# CC2650_Protoboard.net
KiCad netlist of a schematic drawn in EAGLE
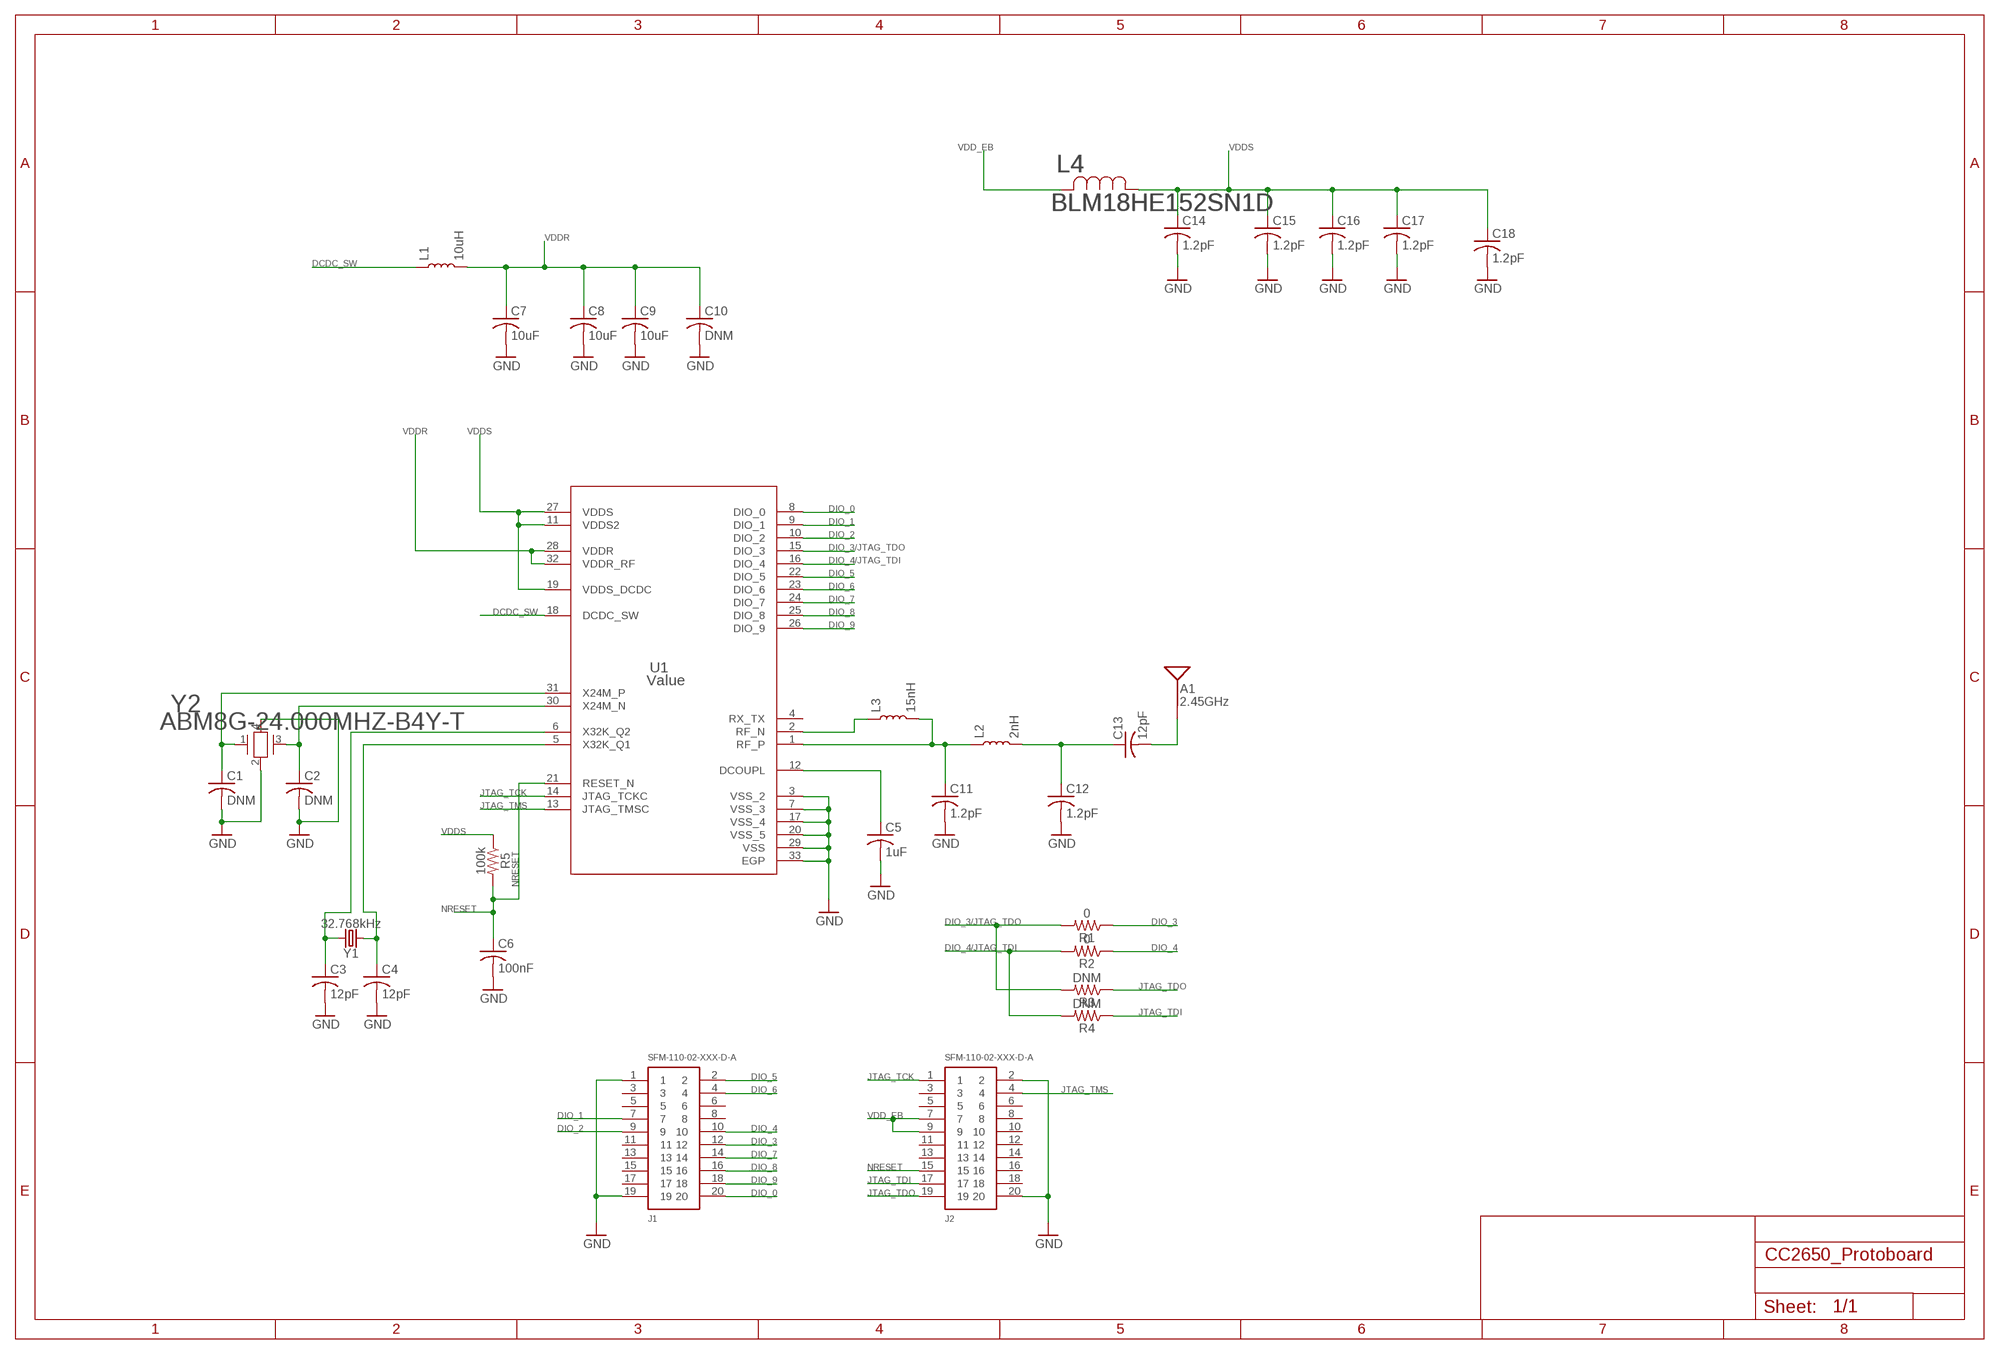
[diagram p0: schematic, sheet 1]

(export (version "E")
  (design (tool "Eeschema 10.0.6"))
  (components
    (comp (ref "A1")
      (value "2.45GHz")
      (footprint "eagle-import:ANT-2.4GHZ-6.5X2.2MM")
      (libsource (lib "eagle-import") (part "ANTENNA2.4GHZ-6.5X2.2MM"))
    )
    (comp (ref "C1")
      (value "DNM")
      (footprint "eagle-import:C0402")
      (libsource (lib "eagle-import") (part "C-USC0402"))
    )
    (comp (ref "C2")
      (value "DNM")
      (footprint "eagle-import:C0402")
      (libsource (lib "eagle-import") (part "C-USC0402"))
    )
    (comp (ref "C3")
      (value "12pF")
      (footprint "eagle-import:C0402")
      (libsource (lib "eagle-import") (part "C-USC0402"))
    )
    (comp (ref "C4")
      (value "12pF")
      (footprint "eagle-import:C0402")
      (libsource (lib "eagle-import") (part "C-USC0402"))
    )
    (comp (ref "C5")
      (value "1uF")
      (footprint "eagle-import:C0402")
      (libsource (lib "eagle-import") (part "C-USC0402"))
    )
    (comp (ref "C6")
      (value "100nF")
      (footprint "eagle-import:C0402")
      (libsource (lib "eagle-import") (part "C-USC0402"))
    )
    (comp (ref "C7")
      (value "10uF")
      (footprint "eagle-import:C0402")
      (libsource (lib "eagle-import") (part "C-USC0402"))
    )
    (comp (ref "C8")
      (value "10uF")
      (footprint "eagle-import:C0402")
      (libsource (lib "eagle-import") (part "C-USC0402"))
    )
    (comp (ref "C9")
      (value "10uF")
      (footprint "eagle-import:C0402")
      (libsource (lib "eagle-import") (part "C-USC0402"))
    )
    (comp (ref "C10")
      (value "DNM")
      (footprint "eagle-import:C0402")
      (libsource (lib "eagle-import") (part "C-USC0402"))
    )
    (comp (ref "C11")
      (value "1.2pF")
      (footprint "eagle-import:C0402")
      (libsource (lib "eagle-import") (part "C-USC0402"))
    )
    (comp (ref "C12")
      (value "1.2pF")
      (footprint "eagle-import:C0402")
      (libsource (lib "eagle-import") (part "C-USC0402"))
    )
    (comp (ref "C13")
      (value "12pF")
      (footprint "eagle-import:C0402")
      (libsource (lib "eagle-import") (part "C-USC0402"))
    )
    (comp (ref "C14")
      (value "1.2pF")
      (footprint "eagle-import:C0402")
      (libsource (lib "eagle-import") (part "C-USC0402"))
    )
    (comp (ref "C15")
      (value "1.2pF")
      (footprint "eagle-import:C0402")
      (libsource (lib "eagle-import") (part "C-USC0402"))
    )
    (comp (ref "C16")
      (value "1.2pF")
      (footprint "eagle-import:C0402")
      (libsource (lib "eagle-import") (part "C-USC0402"))
    )
    (comp (ref "C17")
      (value "1.2pF")
      (footprint "eagle-import:C0402")
      (libsource (lib "eagle-import") (part "C-USC0402"))
    )
    (comp (ref "C18")
      (value "1.2pF")
      (footprint "eagle-import:C0402")
      (libsource (lib "eagle-import") (part "C-USC0402"))
    )
    (comp (ref "J1")
      (value "SFM-110-02-XXX-D-A")
      (footprint "eagle-import:SFM-110-02-XXX-D-A")
      (libsource (lib "eagle-import") (part "SFM-110-02-XXX-D-A"))
    )
    (comp (ref "J2")
      (value "SFM-110-02-XXX-D-A")
      (footprint "eagle-import:SFM-110-02-XXX-D-A")
      (libsource (lib "eagle-import") (part "SFM-110-02-XXX-D-A"))
    )
    (comp (ref "L1")
      (value "10uH")
      (footprint "eagle-import:0402")
      (libsource (lib "eagle-import") (part "INDUCTOR-0402-3.9NH"))
    )
    (comp (ref "L2")
      (value "2nH")
      (footprint "eagle-import:0402")
      (libsource (lib "eagle-import") (part "INDUCTOR-0402-3.9NH"))
    )
    (comp (ref "L3")
      (value "15nH")
      (footprint "eagle-import:0402")
      (libsource (lib "eagle-import") (part "INDUCTOR-0402-3.9NH"))
    )
    (comp (ref "L4")
      (value "BLM18HE152SN1D")
      (footprint "eagle-import:IND_BLM18_0603")
      (libsource (lib "eagle-import") (part "BLM18HE152SN1D"))
    )
    (comp (ref "R1")
      (value "0")
      (footprint "eagle-import:0603")
      (libsource (lib "eagle-import") (part "0.05OHM-0603-1/5W-1%"))
    )
    (comp (ref "R2")
      (value "0")
      (footprint "eagle-import:0603")
      (libsource (lib "eagle-import") (part "0.05OHM-0603-1/5W-1%"))
    )
    (comp (ref "R3")
      (value "DNM")
      (footprint "eagle-import:0603")
      (libsource (lib "eagle-import") (part "0.05OHM-0603-1/5W-1%"))
    )
    (comp (ref "R4")
      (value "DNM")
      (footprint "eagle-import:0603")
      (libsource (lib "eagle-import") (part "0.05OHM-0603-1/5W-1%"))
    )
    (comp (ref "R5")
      (value "100k")
      (footprint "eagle-import:0603")
      (libsource (lib "eagle-import") (part "0.05OHM-0603-1/5W-1%"))
    )
    (comp (ref "U1")
      (value "Value")
      (footprint "eagle-import:RSM0032B")
      (fields (field (name "MANUFACTURER") "Texas Instruments") (field (name "PARTNUMBER") "CC2640R2FRSMR"))
      (libsource (lib "eagle-import") (part "CC2640R2FRSMR"))
    )
    (comp (ref "Y1")
      (value "32.768kHz")
      (footprint "eagle-import:CRYSTAL-SMD-3.2X1.5MM")
      (libsource (lib "eagle-import") (part "CRYSTAL-32.768KHZSMD-3.2X1.5"))
    )
    (comp (ref "Y2")
      (value "ABM8G-24.000MHZ-B4Y-T")
      (footprint "eagle-import:CRYSTAL_ABM8G")
      (fields (field (name "MANUFACTURER_PART_NUMBER") "ABM8G24.000MHZB4YT"))
      (libsource (lib "eagle-import") (part "ABM8G-24.000MHZ-B4Y-T"))
    )
  )
  (nets
    (net (code "1") (name "/DCDC_SW") (class "Default")
      (node (ref "L1") (pin "1") (pinfunction "1_1") (pintype "passive"))
      (node (ref "U1") (pin "18") (pinfunction "DCDC_SW_18") (pintype "power_in"))
    )
    (net (code "2") (name "/DIO_0") (class "Default")
      (node (ref "J1") (pin "20") (pinfunction "20_20") (pintype "bidirectional"))
      (node (ref "U1") (pin "8") (pinfunction "DIO_0_8") (pintype "bidirectional"))
    )
    (net (code "3") (name "/DIO_1") (class "Default")
      (node (ref "J1") (pin "7") (pinfunction "7_7") (pintype "bidirectional"))
      (node (ref "U1") (pin "9") (pinfunction "DIO_1_9") (pintype "bidirectional"))
    )
    (net (code "4") (name "/DIO_2") (class "Default")
      (node (ref "J1") (pin "9") (pinfunction "9_9") (pintype "bidirectional"))
      (node (ref "U1") (pin "10") (pinfunction "DIO_2_10") (pintype "bidirectional"))
    )
    (net (code "5") (name "/DIO_3") (class "Default")
      (node (ref "J1") (pin "12") (pinfunction "12_12") (pintype "bidirectional"))
      (node (ref "R1") (pin "1") (pinfunction "1_1") (pintype "passive"))
    )
    (net (code "6") (name "/DIO_3{slash}JTAG_TDO") (class "Default")
      (node (ref "R1") (pin "2") (pinfunction "2_2") (pintype "passive"))
      (node (ref "R3") (pin "2") (pinfunction "2_2") (pintype "passive"))
      (node (ref "U1") (pin "15") (pinfunction "DIO_3_15") (pintype "bidirectional"))
    )
    (net (code "7") (name "/DIO_4") (class "Default")
      (node (ref "J1") (pin "10") (pinfunction "10_10") (pintype "bidirectional"))
      (node (ref "R2") (pin "1") (pinfunction "1_1") (pintype "passive"))
    )
    (net (code "8") (name "/DIO_4{slash}JTAG_TDI") (class "Default")
      (node (ref "R2") (pin "2") (pinfunction "2_2") (pintype "passive"))
      (node (ref "R4") (pin "2") (pinfunction "2_2") (pintype "passive"))
      (node (ref "U1") (pin "16") (pinfunction "DIO_4_16") (pintype "bidirectional"))
    )
    (net (code "9") (name "/DIO_5") (class "Default")
      (node (ref "J1") (pin "2") (pinfunction "2_2") (pintype "bidirectional"))
      (node (ref "U1") (pin "22") (pinfunction "DIO_5_22") (pintype "bidirectional"))
    )
    (net (code "10") (name "/DIO_6") (class "Default")
      (node (ref "J1") (pin "4") (pinfunction "4_4") (pintype "bidirectional"))
      (node (ref "U1") (pin "23") (pinfunction "DIO_6_23") (pintype "bidirectional"))
    )
    (net (code "11") (name "/DIO_7") (class "Default")
      (node (ref "J1") (pin "14") (pinfunction "14_14") (pintype "bidirectional"))
      (node (ref "U1") (pin "24") (pinfunction "DIO_7_24") (pintype "bidirectional"))
    )
    (net (code "12") (name "/DIO_8") (class "Default")
      (node (ref "J1") (pin "16") (pinfunction "16_16") (pintype "bidirectional"))
      (node (ref "U1") (pin "25") (pinfunction "DIO_8_25") (pintype "bidirectional"))
    )
    (net (code "13") (name "/DIO_9") (class "Default")
      (node (ref "J1") (pin "18") (pinfunction "18_18") (pintype "bidirectional"))
      (node (ref "U1") (pin "26") (pinfunction "DIO_9_26") (pintype "bidirectional"))
    )
    (net (code "14") (name "/JTAG_TCK") (class "Default")
      (node (ref "J2") (pin "1") (pinfunction "1_1") (pintype "bidirectional"))
      (node (ref "U1") (pin "14") (pinfunction "JTAG_TCKC_14") (pintype "passive"))
    )
    (net (code "15") (name "/JTAG_TDI") (class "Default")
      (node (ref "J2") (pin "17") (pinfunction "17_17") (pintype "bidirectional"))
      (node (ref "R4") (pin "1") (pinfunction "1_1") (pintype "passive"))
    )
    (net (code "16") (name "/JTAG_TDO") (class "Default")
      (node (ref "J2") (pin "19") (pinfunction "19_19") (pintype "bidirectional"))
      (node (ref "R3") (pin "1") (pinfunction "1_1") (pintype "passive"))
    )
    (net (code "17") (name "/JTAG_TMS") (class "Default")
      (node (ref "J2") (pin "4") (pinfunction "4_4") (pintype "bidirectional"))
      (node (ref "U1") (pin "13") (pinfunction "JTAG_TMSC_13") (pintype "passive"))
    )
    (net (code "18") (name "/NRESET") (class "Default")
      (node (ref "C6") (pin "1") (pinfunction "1_1") (pintype "passive"))
      (node (ref "J2") (pin "15") (pinfunction "15_15") (pintype "bidirectional"))
      (node (ref "R5") (pin "2") (pinfunction "2_2") (pintype "passive"))
      (node (ref "U1") (pin "21") (pinfunction "RESET_N_21") (pintype "input"))
    )
    (net (code "19") (name "/VDDR") (class "Default")
      (node (ref "C10") (pin "1") (pinfunction "1_1") (pintype "passive"))
      (node (ref "C7") (pin "1") (pinfunction "1_1") (pintype "passive"))
      (node (ref "C8") (pin "1") (pinfunction "1_1") (pintype "passive"))
      (node (ref "C9") (pin "1") (pinfunction "1_1") (pintype "passive"))
      (node (ref "L1") (pin "2") (pinfunction "2_2") (pintype "passive"))
      (node (ref "U1") (pin "28") (pinfunction "VDDR_28") (pintype "power_in"))
      (node (ref "U1") (pin "32") (pinfunction "VDDR_RF_32") (pintype "power_in"))
    )
    (net (code "20") (name "/VDDS") (class "Default")
      (node (ref "C14") (pin "1") (pinfunction "1_1") (pintype "passive"))
      (node (ref "C15") (pin "1") (pinfunction "1_1") (pintype "passive"))
      (node (ref "C16") (pin "1") (pinfunction "1_1") (pintype "passive"))
      (node (ref "C17") (pin "1") (pinfunction "1_1") (pintype "passive"))
      (node (ref "C18") (pin "1") (pinfunction "1_1") (pintype "passive"))
      (node (ref "L4") (pin "1") (pinfunction "1_1") (pintype "passive"))
      (node (ref "R5") (pin "1") (pinfunction "1_1") (pintype "passive"))
      (node (ref "U1") (pin "11") (pinfunction "VDDS2_11") (pintype "power_in"))
      (node (ref "U1") (pin "19") (pinfunction "VDDS_DCDC_19") (pintype "power_in"))
      (node (ref "U1") (pin "27") (pinfunction "VDDS_27") (pintype "power_in"))
    )
    (net (code "21") (name "/VDD_EB") (class "Default")
      (node (ref "J2") (pin "7") (pinfunction "7_7") (pintype "bidirectional"))
      (node (ref "J2") (pin "9") (pinfunction "9_9") (pintype "bidirectional"))
      (node (ref "L4") (pin "2") (pinfunction "2_2") (pintype "passive"))
    )
    (net (code "22") (name "GND") (class "Default")
      (node (ref "C1") (pin "2") (pinfunction "2_2") (pintype "passive"))
      (node (ref "C10") (pin "2") (pinfunction "2_2") (pintype "passive"))
      (node (ref "C11") (pin "2") (pinfunction "2_2") (pintype "passive"))
      (node (ref "C12") (pin "2") (pinfunction "2_2") (pintype "passive"))
      (node (ref "C14") (pin "2") (pinfunction "2_2") (pintype "passive"))
      (node (ref "C15") (pin "2") (pinfunction "2_2") (pintype "passive"))
      (node (ref "C16") (pin "2") (pinfunction "2_2") (pintype "passive"))
      (node (ref "C17") (pin "2") (pinfunction "2_2") (pintype "passive"))
      (node (ref "C18") (pin "2") (pinfunction "2_2") (pintype "passive"))
      (node (ref "C2") (pin "2") (pinfunction "2_2") (pintype "passive"))
      (node (ref "C3") (pin "2") (pinfunction "2_2") (pintype "passive"))
      (node (ref "C4") (pin "2") (pinfunction "2_2") (pintype "passive"))
      (node (ref "C5") (pin "2") (pinfunction "2_2") (pintype "passive"))
      (node (ref "C6") (pin "2") (pinfunction "2_2") (pintype "passive"))
      (node (ref "C7") (pin "2") (pinfunction "2_2") (pintype "passive"))
      (node (ref "C8") (pin "2") (pinfunction "2_2") (pintype "passive"))
      (node (ref "C9") (pin "2") (pinfunction "2_2") (pintype "passive"))
      (node (ref "J1") (pin "1") (pinfunction "1_1") (pintype "bidirectional"))
      (node (ref "J1") (pin "19") (pinfunction "19_19") (pintype "bidirectional"))
      (node (ref "J2") (pin "2") (pinfunction "2_2") (pintype "bidirectional"))
      (node (ref "J2") (pin "20") (pinfunction "20_20") (pintype "bidirectional"))
      (node (ref "U1") (pin "17") (pinfunction "VSS_4_17") (pintype "power_in"))
      (node (ref "U1") (pin "20") (pinfunction "VSS_5_20") (pintype "power_in"))
      (node (ref "U1") (pin "29") (pinfunction "VSS_29") (pintype "power_in"))
      (node (ref "U1") (pin "3") (pinfunction "VSS_2_3") (pintype "power_in"))
      (node (ref "U1") (pin "33") (pinfunction "EGP_33") (pintype "power_in"))
      (node (ref "U1") (pin "7") (pinfunction "VSS_3_7") (pintype "power_in"))
      (node (ref "Y2") (pin "2") (pinfunction "2_2") (pintype "passive"))
      (node (ref "Y2") (pin "4") (pinfunction "4_4") (pintype "passive"))
    )
    (net (code "23") (name "Net-(A1-SIGNAL)") (class "Default")
      (node (ref "A1") (pin "FEED") (pinfunction "SIGNAL_FEED") (pintype "bidirectional"))
      (node (ref "C13") (pin "2") (pinfunction "2_2") (pintype "passive"))
    )
    (net (code "24") (name "Net-(C12-Pad1)") (class "Default")
      (node (ref "C12") (pin "1") (pinfunction "1_1") (pintype "passive"))
      (node (ref "C13") (pin "1") (pinfunction "1_1") (pintype "passive"))
      (node (ref "L2") (pin "2") (pinfunction "2_2") (pintype "passive"))
    )
    (net (code "25") (name "Net-(U1-DCOUPL)") (class "Default")
      (node (ref "C5") (pin "1") (pinfunction "1_1") (pintype "passive"))
      (node (ref "U1") (pin "12") (pinfunction "DCOUPL_12") (pintype "passive"))
    )
    (net (code "26") (name "Net-(U1-RF_N)") (class "Default")
      (node (ref "L3") (pin "1") (pinfunction "1_1") (pintype "passive"))
      (node (ref "U1") (pin "2") (pinfunction "RF_N_2") (pintype "bidirectional"))
    )
    (net (code "27") (name "Net-(U1-RF_P)") (class "Default")
      (node (ref "C11") (pin "1") (pinfunction "1_1") (pintype "passive"))
      (node (ref "L2") (pin "1") (pinfunction "1_1") (pintype "passive"))
      (node (ref "L3") (pin "2") (pinfunction "2_2") (pintype "passive"))
      (node (ref "U1") (pin "1") (pinfunction "RF_P_1") (pintype "bidirectional"))
    )
    (net (code "28") (name "Net-(U1-X24M_N)") (class "Default")
      (node (ref "C2") (pin "1") (pinfunction "1_1") (pintype "passive"))
      (node (ref "U1") (pin "30") (pinfunction "X24M_N_30") (pintype "passive"))
      (node (ref "Y2") (pin "3") (pinfunction "3_3") (pintype "passive"))
    )
    (net (code "29") (name "Net-(U1-X24M_P)") (class "Default")
      (node (ref "C1") (pin "1") (pinfunction "1_1") (pintype "passive"))
      (node (ref "U1") (pin "31") (pinfunction "X24M_P_31") (pintype "passive"))
      (node (ref "Y2") (pin "1") (pinfunction "1_1") (pintype "passive"))
    )
    (net (code "30") (name "Net-(U1-X32K_Q1)") (class "Default")
      (node (ref "C4") (pin "1") (pinfunction "1_1") (pintype "passive"))
      (node (ref "U1") (pin "5") (pinfunction "X32K_Q1_5") (pintype "output"))
      (node (ref "Y1") (pin "P$1") (pinfunction "1_P$1") (pintype "passive"))
    )
    (net (code "31") (name "Net-(U1-X32K_Q2)") (class "Default")
      (node (ref "C3") (pin "1") (pinfunction "1_1") (pintype "passive"))
      (node (ref "U1") (pin "6") (pinfunction "X32K_Q2_6") (pintype "output"))
      (node (ref "Y1") (pin "P$2") (pinfunction "2_P$2") (pintype "passive"))
    )
    (net (code "32") (name "unconnected-(J1-Pad3)") (class "Default")
      (node (ref "J1") (pin "3") (pinfunction "3_3") (pintype "bidirectional"))
    )
    (net (code "33") (name "unconnected-(J1-Pad5)") (class "Default")
      (node (ref "J1") (pin "5") (pinfunction "5_5") (pintype "bidirectional"))
    )
    (net (code "34") (name "unconnected-(J1-Pad6)") (class "Default")
      (node (ref "J1") (pin "6") (pinfunction "6_6") (pintype "bidirectional"))
    )
    (net (code "35") (name "unconnected-(J1-Pad8)") (class "Default")
      (node (ref "J1") (pin "8") (pinfunction "8_8") (pintype "bidirectional"))
    )
    (net (code "36") (name "unconnected-(J1-Pad11)") (class "Default")
      (node (ref "J1") (pin "11") (pinfunction "11_11") (pintype "bidirectional"))
    )
    (net (code "37") (name "unconnected-(J1-Pad13)") (class "Default")
      (node (ref "J1") (pin "13") (pinfunction "13_13") (pintype "bidirectional"))
    )
    (net (code "38") (name "unconnected-(J1-Pad15)") (class "Default")
      (node (ref "J1") (pin "15") (pinfunction "15_15") (pintype "bidirectional"))
    )
    (net (code "39") (name "unconnected-(J1-Pad17)") (class "Default")
      (node (ref "J1") (pin "17") (pinfunction "17_17") (pintype "bidirectional"))
    )
    (net (code "40") (name "unconnected-(J2-Pad3)") (class "Default")
      (node (ref "J2") (pin "3") (pinfunction "3_3") (pintype "bidirectional"))
    )
    (net (code "41") (name "unconnected-(J2-Pad5)") (class "Default")
      (node (ref "J2") (pin "5") (pinfunction "5_5") (pintype "bidirectional"))
    )
    (net (code "42") (name "unconnected-(J2-Pad6)") (class "Default")
      (node (ref "J2") (pin "6") (pinfunction "6_6") (pintype "bidirectional"))
    )
    (net (code "43") (name "unconnected-(J2-Pad8)") (class "Default")
      (node (ref "J2") (pin "8") (pinfunction "8_8") (pintype "bidirectional"))
    )
    (net (code "44") (name "unconnected-(J2-Pad10)") (class "Default")
      (node (ref "J2") (pin "10") (pinfunction "10_10") (pintype "bidirectional"))
    )
    (net (code "45") (name "unconnected-(J2-Pad11)") (class "Default")
      (node (ref "J2") (pin "11") (pinfunction "11_11") (pintype "bidirectional"))
    )
    (net (code "46") (name "unconnected-(J2-Pad12)") (class "Default")
      (node (ref "J2") (pin "12") (pinfunction "12_12") (pintype "bidirectional"))
    )
    (net (code "47") (name "unconnected-(J2-Pad13)") (class "Default")
      (node (ref "J2") (pin "13") (pinfunction "13_13") (pintype "bidirectional"))
    )
    (net (code "48") (name "unconnected-(J2-Pad14)") (class "Default")
      (node (ref "J2") (pin "14") (pinfunction "14_14") (pintype "bidirectional"))
    )
    (net (code "49") (name "unconnected-(J2-Pad16)") (class "Default")
      (node (ref "J2") (pin "16") (pinfunction "16_16") (pintype "bidirectional"))
    )
    (net (code "50") (name "unconnected-(J2-Pad18)") (class "Default")
      (node (ref "J2") (pin "18") (pinfunction "18_18") (pintype "bidirectional"))
    )
    (net (code "51") (name "unconnected-(U1-RX_TX-Pad4)") (class "Default")
      (node (ref "U1") (pin "4") (pinfunction "RX_TX_4") (pintype "input"))
    )
  )
)
